# MG.net
KiCad netlist of a schematic drawn in EAGLE
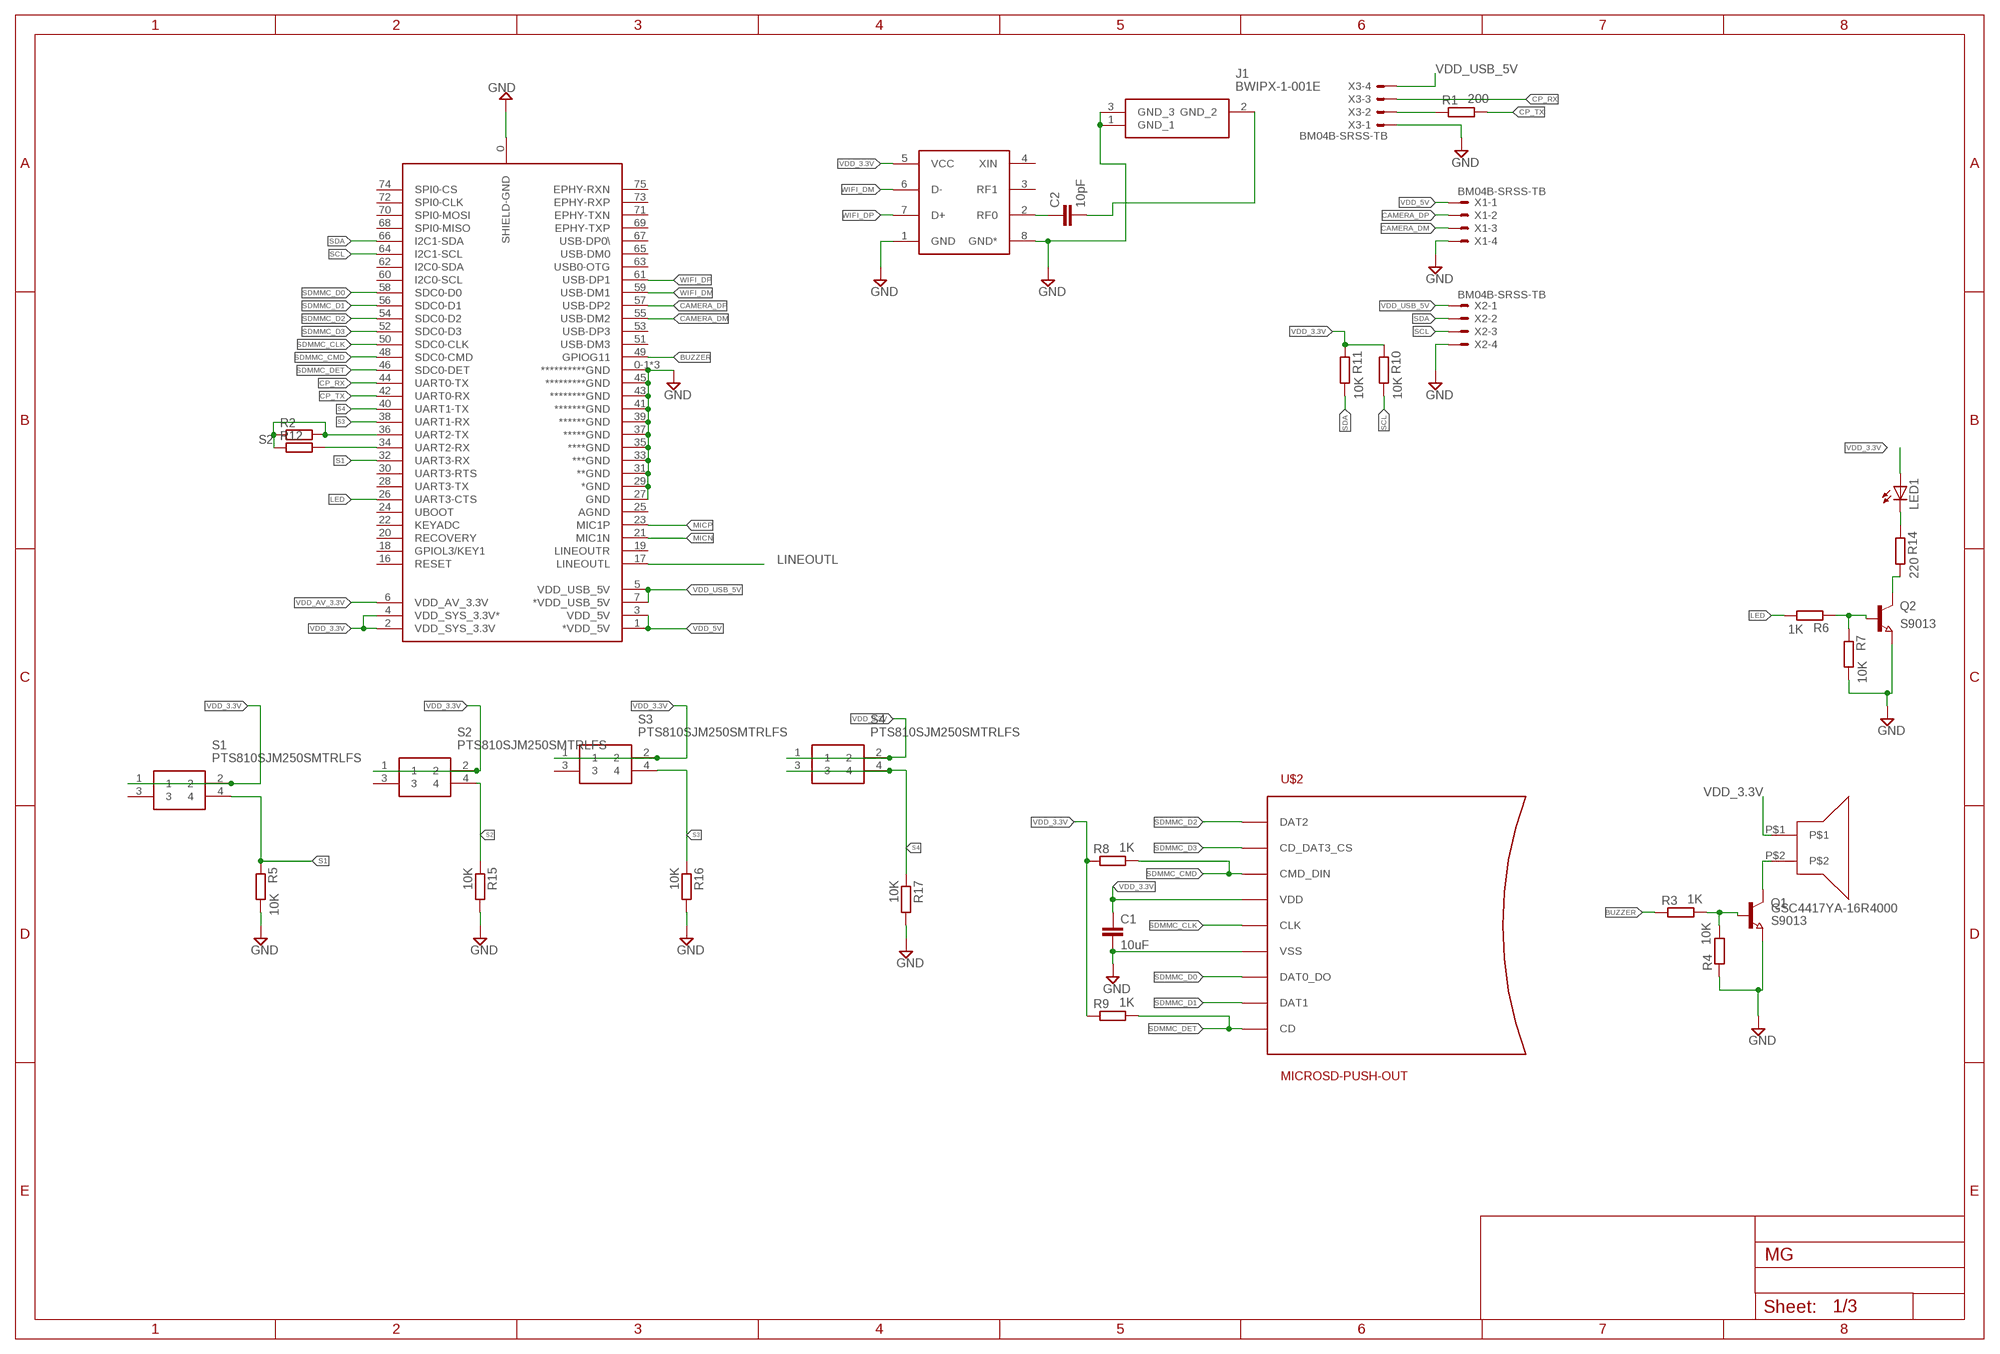
[diagram p0: schematic, sheet 1]
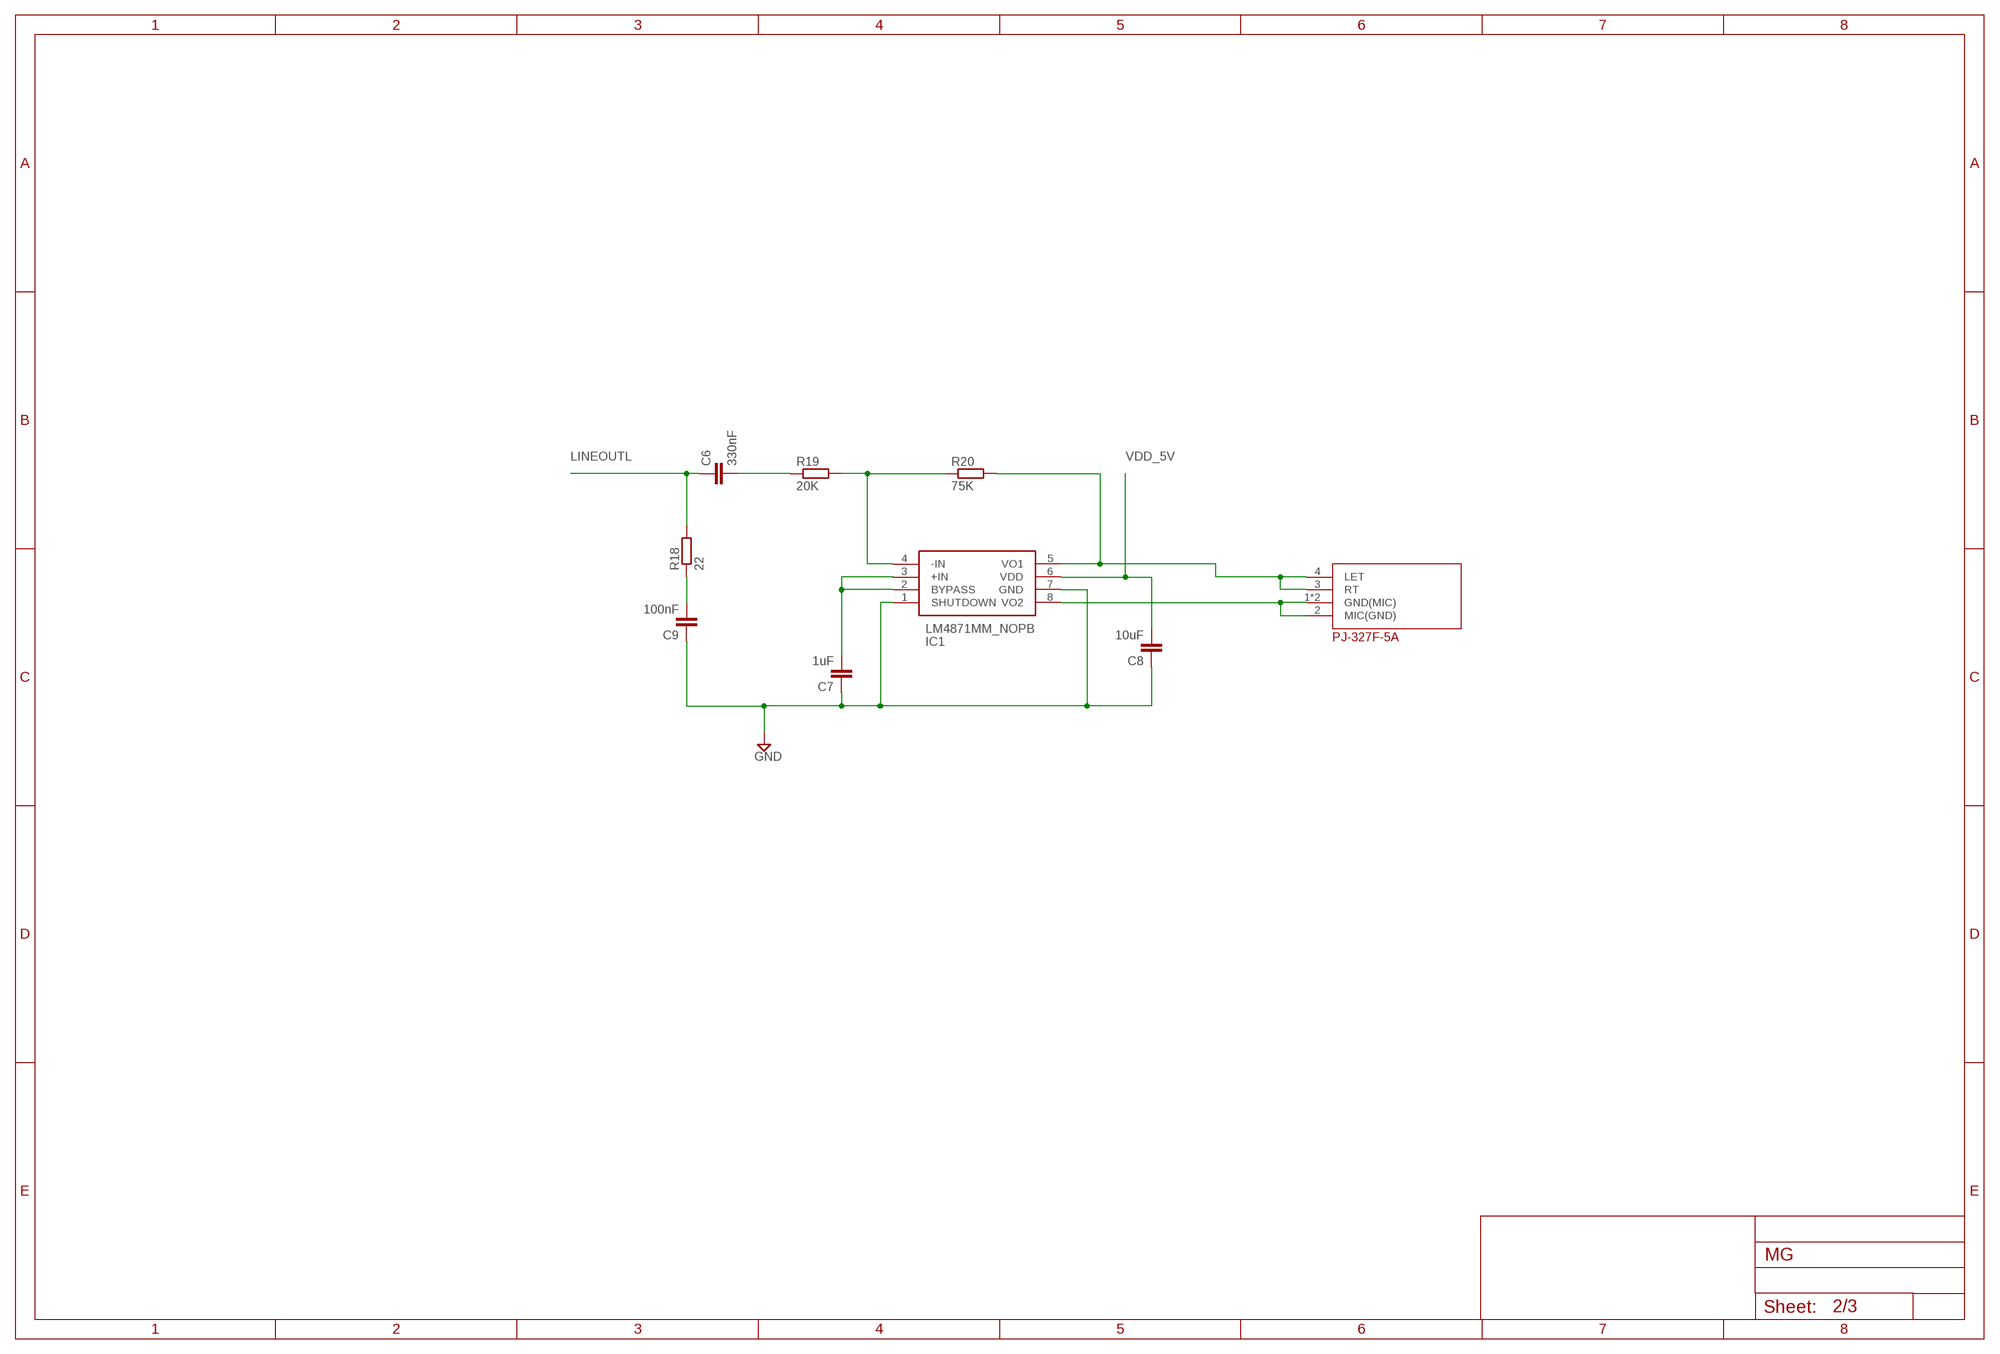
[diagram p1: schematic, sheet 2]
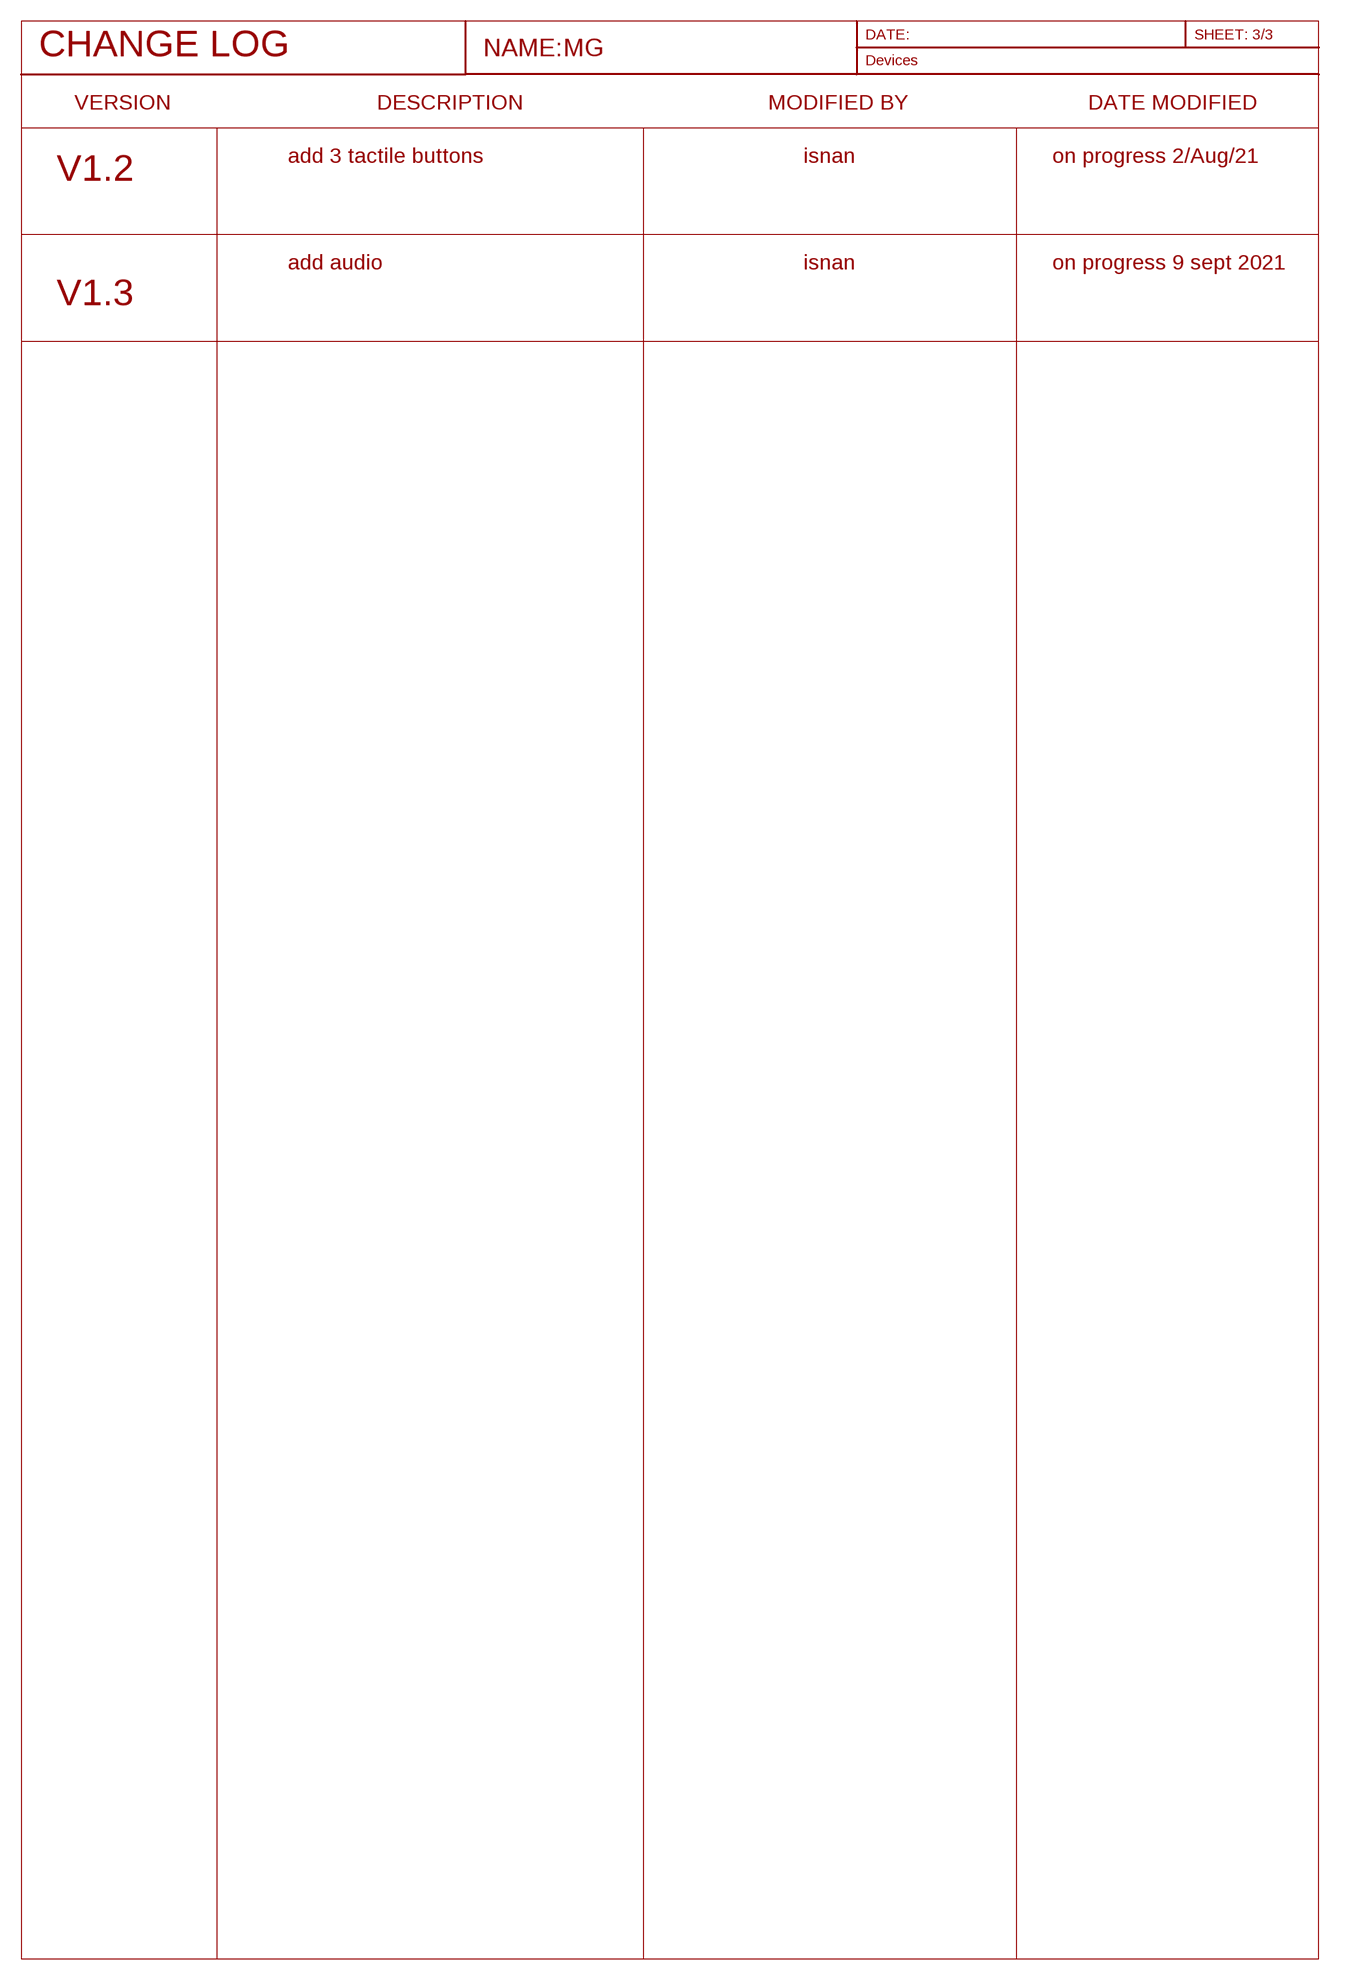
[diagram p2: schematic, sheet 3]

(export (version "E")
  (design (tool "Eeschema 10.0.6"))
  (components
    (comp (ref "C6")
      (value "330nF")
      (footprint "eagle-import:C0603")
      (libsource (lib "eagle-import") (part "C-EUC0603"))
    )
    (comp (ref "C7")
      (value "1uF")
      (footprint "eagle-import:C0603")
      (libsource (lib "eagle-import") (part "C-EUC0603"))
    )
    (comp (ref "C8")
      (value "10uF")
      (footprint "eagle-import:C0603")
      (libsource (lib "eagle-import") (part "C-EUC0603"))
    )
    (comp (ref "C9")
      (value "100nF")
      (footprint "eagle-import:C0603")
      (libsource (lib "eagle-import") (part "C-EUC0603"))
    )
    (comp (ref "IC1")
      (value "LM4871MM_NOPB")
      (footprint "eagle-import:SOP65P490X110-8N")
      (fields
        (field (name "MANUFACTURER_PART_NUMBER") "LM4871MM/NOPB")
        (field (name "MOUSER_PART_NUMBER") "926-LM4871MM/NOPB")
      )
      (libsource (lib "eagle-import") (part "LM4871MM_NOPB"))
    )
    (comp (ref "R18")
      (value "22")
      (footprint "eagle-import:R0603")
      (libsource (lib "eagle-import") (part "R-EU_R0603"))
    )
    (comp (ref "R19")
      (value "20K")
      (footprint "eagle-import:R0603")
      (libsource (lib "eagle-import") (part "R-EU_R0603"))
    )
    (comp (ref "R20")
      (value "75K")
      (footprint "eagle-import:R0603")
      (libsource (lib "eagle-import") (part "R-EU_R0603"))
    )
    (comp (ref "U$7")
      (value "PJ-327F-5A")
      (footprint "eagle-import:PJ-327F-5A")
      (libsource (lib "eagle-import") (part "PJ-327F-5A"))
    )
    (comp (ref "C1")
      (value "10uF")
      (footprint "eagle-import:C0603")
      (libsource (lib "eagle-import") (part "C-EUC0603"))
    )
    (comp (ref "C2")
      (value "10pF")
      (footprint "eagle-import:C0603")
      (libsource (lib "eagle-import") (part "C-EUC0603"))
    )
    (comp (ref "J1")
      (value "BWIPX-1-001E")
      (footprint "eagle-import:BWIPX1001E")
      (libsource (lib "eagle-import") (part "BWIPX-1-001E"))
    )
    (comp (ref "LED1")
      (value "LEDSML0603")
      (footprint "eagle-import:SML0603")
      (libsource (lib "eagle-import") (part "LEDSML0603"))
    )
    (comp (ref "Q1")
      (value "S9013")
      (footprint "eagle-import:SOT23")
      (libsource (lib "eagle-import") (part "NPN-TRANSISTOR_SOT23"))
    )
    (comp (ref "Q2")
      (value "S9013")
      (footprint "eagle-import:SOT23")
      (libsource (lib "eagle-import") (part "NPN-TRANSISTOR_SOT23"))
    )
    (comp (ref "R1")
      (value "200")
      (footprint "eagle-import:R0603")
      (libsource (lib "eagle-import") (part "R-EU_R0603"))
    )
    (comp (ref "R2")
      (value "R-EU_R0201")
      (footprint "eagle-import:R0201")
      (libsource (lib "eagle-import") (part "R-EU_R0201"))
    )
    (comp (ref "R3")
      (value "1K")
      (footprint "eagle-import:R0603")
      (libsource (lib "eagle-import") (part "R-EU_R0603"))
    )
    (comp (ref "R4")
      (value "10K")
      (footprint "eagle-import:R0603")
      (libsource (lib "eagle-import") (part "R-EU_R0603"))
    )
    (comp (ref "R5")
      (value "10K")
      (footprint "eagle-import:R0603")
      (libsource (lib "eagle-import") (part "R-EU_R0603"))
    )
    (comp (ref "R6")
      (value "1K")
      (footprint "eagle-import:R0603")
      (libsource (lib "eagle-import") (part "R-EU_R0603"))
    )
    (comp (ref "R7")
      (value "10K")
      (footprint "eagle-import:R0603")
      (libsource (lib "eagle-import") (part "R-EU_R0603"))
    )
    (comp (ref "R8")
      (value "1K")
      (footprint "eagle-import:R0603")
      (libsource (lib "eagle-import") (part "R-EU_R0603"))
    )
    (comp (ref "R9")
      (value "1K")
      (footprint "eagle-import:R0603")
      (libsource (lib "eagle-import") (part "R-EU_R0603"))
    )
    (comp (ref "R10")
      (value "10K")
      (footprint "eagle-import:R0603")
      (libsource (lib "eagle-import") (part "R-EU_R0603"))
    )
    (comp (ref "R11")
      (value "10K")
      (footprint "eagle-import:R0603")
      (libsource (lib "eagle-import") (part "R-EU_R0603"))
    )
    (comp (ref "R12")
      (value "R-EU_R0201")
      (footprint "eagle-import:R0201")
      (libsource (lib "eagle-import") (part "R-EU_R0201"))
    )
    (comp (ref "R14")
      (value "220")
      (footprint "eagle-import:R0603")
      (libsource (lib "eagle-import") (part "R-EU_R0603"))
    )
    (comp (ref "R15")
      (value "10K")
      (footprint "eagle-import:R0603")
      (libsource (lib "eagle-import") (part "R-EU_R0603"))
    )
    (comp (ref "R16")
      (value "10K")
      (footprint "eagle-import:R0603")
      (libsource (lib "eagle-import") (part "R-EU_R0603"))
    )
    (comp (ref "R17")
      (value "10K")
      (footprint "eagle-import:R0603")
      (libsource (lib "eagle-import") (part "R-EU_R0603"))
    )
    (comp (ref "S1")
      (value "PTS810SJM250SMTRLFS")
      (footprint "eagle-import:PTS810SJG250SMTRLFS")
      (fields (field (name "MOUSER_PART_NUMBER") "611-PTS810SJM250SMTR"))
      (libsource (lib "eagle-import") (part "PTS810SJM250SMTRLFS"))
    )
    (comp (ref "S2")
      (value "PTS810SJM250SMTRLFS")
      (footprint "eagle-import:PTS810SJG250SMTRLFS")
      (fields (field (name "MOUSER_PART_NUMBER") "611-PTS810SJM250SMTR"))
      (libsource (lib "eagle-import") (part "PTS810SJM250SMTRLFS"))
    )
    (comp (ref "S3")
      (value "PTS810SJM250SMTRLFS")
      (footprint "eagle-import:PTS810SJG250SMTRLFS")
      (fields (field (name "MOUSER_PART_NUMBER") "611-PTS810SJM250SMTR"))
      (libsource (lib "eagle-import") (part "PTS810SJM250SMTRLFS"))
    )
    (comp (ref "S4")
      (value "PTS810SJM250SMTRLFS")
      (footprint "eagle-import:PTS810SJG250SMTRLFS")
      (fields (field (name "MOUSER_PART_NUMBER") "611-PTS810SJM250SMTR"))
      (libsource (lib "eagle-import") (part "PTS810SJM250SMTRLFS"))
    )
    (comp (ref "U$1")
      (value "QUANTUM-CORE")
      (footprint "eagle-import:QUANTUM-QUARK-N")
      (libsource (lib "eagle-import") (part "QUANTUM-CORE"))
    )
    (comp (ref "U$2")
      (value "MICROSD-PUSH-OUT")
      (footprint "eagle-import:MICROSD-PUSH-OUT")
      (libsource (lib "eagle-import") (part "MICROSD-PUSH-OUT"))
    )
    (comp (ref "U$3")
      (value "WIFI-BT-RTL8723BU")
      (footprint "eagle-import:USB-WIFI-BT-RTL8723BU")
      (libsource (lib "eagle-import") (part "WIFI-BT-RTL8723BU"))
    )
    (comp (ref "U$4")
      (value "GSC4417YA-16R4000")
      (footprint "eagle-import:GSC4417YA-16R4000")
      (libsource (lib "eagle-import") (part "GSC4417YA-16R4000"))
    )
    (comp (ref "X1")
      (value "BM04B-SRSS-TB")
      (footprint "eagle-import:BM04B-SRSS-TB")
      (libsource (lib "eagle-import") (part "?M04B-SRSS-TBB"))
    )
    (comp (ref "X2")
      (value "BM04B-SRSS-TB")
      (footprint "eagle-import:BM04B-SRSS-TB")
      (libsource (lib "eagle-import") (part "?M04B-SRSS-TBB"))
    )
    (comp (ref "X3")
      (value "BM04B-SRSS-TB")
      (footprint "eagle-import:BM04B-SRSS-TB")
      (libsource (lib "eagle-import") (part "?M04B-SRSS-TBB"))
    )
  )
  (nets
    (net (code "1") (name "BUZZER") (class "Default")
      (node (ref "R3") (pin "1") (pinfunction "1_1") (pintype "passive"))
      (node (ref "U$1") (pin "49") (pinfunction "GPIOG11_49") (pintype "bidirectional"))
    )
    (net (code "2") (name "CAMERA_DM") (class "Default")
      (node (ref "U$1") (pin "55") (pinfunction "USB-DM2_55") (pintype "bidirectional"))
      (node (ref "X1") (pin "3") (pinfunction "S_3") (pintype "passive"))
    )
    (net (code "3") (name "CAMERA_DP") (class "Default")
      (node (ref "U$1") (pin "57") (pinfunction "USB-DP2_57") (pintype "bidirectional"))
      (node (ref "X1") (pin "2") (pinfunction "S_2") (pintype "passive"))
    )
    (net (code "4") (name "CP_RX") (class "Default")
      (node (ref "U$1") (pin "44") (pinfunction "UART0-TX_44") (pintype "bidirectional"))
      (node (ref "X3") (pin "3") (pinfunction "S_3") (pintype "passive"))
    )
    (net (code "5") (name "CP_TX") (class "Default")
      (node (ref "R1") (pin "2") (pinfunction "2_2") (pintype "passive"))
      (node (ref "U$1") (pin "42") (pinfunction "UART0-RX_42") (pintype "bidirectional"))
    )
    (net (code "6") (name "GND") (class "Default")
      (node (ref "C1") (pin "2") (pinfunction "2_2") (pintype "passive"))
      (node (ref "C7") (pin "1") (pinfunction "1_1") (pintype "passive"))
      (node (ref "C8") (pin "1") (pinfunction "1_1") (pintype "passive"))
      (node (ref "C9") (pin "1") (pinfunction "1_1") (pintype "passive"))
      (node (ref "IC1") (pin "1") (pinfunction "SHUTDOWN_1") (pintype "bidirectional"))
      (node (ref "IC1") (pin "7") (pinfunction "GND_7") (pintype "bidirectional"))
      (node (ref "J1") (pin "1") (pinfunction "GND_1_1") (pintype "bidirectional"))
      (node (ref "J1") (pin "3") (pinfunction "GND_3_3") (pintype "bidirectional"))
      (node (ref "Q1") (pin "2") (pinfunction "E_2") (pintype "passive"))
      (node (ref "Q2") (pin "2") (pinfunction "E_2") (pintype "passive"))
      (node (ref "R15") (pin "2") (pinfunction "2_2") (pintype "passive"))
      (node (ref "R16") (pin "2") (pinfunction "2_2") (pintype "passive"))
      (node (ref "R17") (pin "2") (pinfunction "2_2") (pintype "passive"))
      (node (ref "R4") (pin "1") (pinfunction "1_1") (pintype "passive"))
      (node (ref "R5") (pin "2") (pinfunction "2_2") (pintype "passive"))
      (node (ref "R7") (pin "2") (pinfunction "2_2") (pintype "passive"))
      (node (ref "U$1") (pin "0") (pinfunction "SHIELD-GND_0") (pintype "bidirectional"))
      (node (ref "U$1") (pin "0-1") (pinfunction "**********GND_0-1") (pintype "bidirectional"))
      (node (ref "U$1") (pin "0-2") (pinfunction "**********GND_0-2") (pintype "bidirectional"))
      (node (ref "U$1") (pin "27") (pinfunction "GND_27") (pintype "bidirectional"))
      (node (ref "U$1") (pin "29") (pinfunction "*GND_29") (pintype "bidirectional"))
      (node (ref "U$1") (pin "31") (pinfunction "**GND_31") (pintype "bidirectional"))
      (node (ref "U$1") (pin "33") (pinfunction "***GND_33") (pintype "bidirectional"))
      (node (ref "U$1") (pin "35") (pinfunction "****GND_35") (pintype "bidirectional"))
      (node (ref "U$1") (pin "37") (pinfunction "*****GND_37") (pintype "bidirectional"))
      (node (ref "U$1") (pin "39") (pinfunction "******GND_39") (pintype "bidirectional"))
      (node (ref "U$1") (pin "41") (pinfunction "*******GND_41") (pintype "bidirectional"))
      (node (ref "U$1") (pin "43") (pinfunction "********GND_43") (pintype "bidirectional"))
      (node (ref "U$1") (pin "45") (pinfunction "*********GND_45") (pintype "bidirectional"))
      (node (ref "U$1") (pin "47") (pinfunction "**********GND_47") (pintype "bidirectional"))
      (node (ref "U$2") (pin "6") (pinfunction "VSS_6") (pintype "bidirectional"))
      (node (ref "U$2") (pin "G1") (pinfunction "VSS_G1") (pintype "bidirectional"))
      (node (ref "U$2") (pin "G2") (pinfunction "VSS_G2") (pintype "bidirectional"))
      (node (ref "U$2") (pin "G3") (pinfunction "VSS_G3") (pintype "bidirectional"))
      (node (ref "U$2") (pin "G4") (pinfunction "VSS_G4") (pintype "bidirectional"))
      (node (ref "U$3") (pin "1") (pinfunction "GND_1") (pintype "bidirectional"))
      (node (ref "U$3") (pin "8") (pinfunction "GND*_8") (pintype "bidirectional"))
      (node (ref "X1") (pin "4") (pinfunction "S_4") (pintype "passive"))
      (node (ref "X2") (pin "4") (pinfunction "S_4") (pintype "passive"))
      (node (ref "X3") (pin "1") (pinfunction "S_1") (pintype "passive"))
    )
    (net (code "7") (name "LED") (class "Default")
      (node (ref "R6") (pin "2") (pinfunction "2_2") (pintype "passive"))
      (node (ref "U$1") (pin "26") (pinfunction "UART3-CTS_26") (pintype "bidirectional"))
    )
    (net (code "8") (name "LINEOUTL") (class "Default")
      (node (ref "C6") (pin "1") (pinfunction "1_1") (pintype "passive"))
      (node (ref "R18") (pin "2") (pinfunction "2_2") (pintype "passive"))
      (node (ref "U$1") (pin "17") (pinfunction "LINEOUTL_17") (pintype "bidirectional"))
    )
    (net (code "9") (name "MICN") (class "Default")
      (node (ref "U$1") (pin "21") (pinfunction "MIC1N_21") (pintype "bidirectional"))
    )
    (net (code "10") (name "MICP") (class "Default")
      (node (ref "U$1") (pin "23") (pinfunction "MIC1P_23") (pintype "bidirectional"))
    )
    (net (code "11") (name "Net-(C6-Pad2)") (class "Default")
      (node (ref "C6") (pin "2") (pinfunction "2_2") (pintype "passive"))
      (node (ref "R19") (pin "1") (pinfunction "1_1") (pintype "passive"))
    )
    (net (code "12") (name "Net-(C9-Pad2)") (class "Default")
      (node (ref "C9") (pin "2") (pinfunction "2_2") (pintype "passive"))
      (node (ref "R18") (pin "1") (pinfunction "1_1") (pintype "passive"))
    )
    (net (code "13") (name "Net-(IC1-+IN)") (class "Default")
      (node (ref "C7") (pin "2") (pinfunction "2_2") (pintype "passive"))
      (node (ref "IC1") (pin "2") (pinfunction "BYPASS_2") (pintype "bidirectional"))
      (node (ref "IC1") (pin "3") (pinfunction "+IN_3") (pintype "bidirectional"))
    )
    (net (code "14") (name "Net-(IC1--IN)") (class "Default")
      (node (ref "IC1") (pin "4") (pinfunction "-IN_4") (pintype "bidirectional"))
      (node (ref "R19") (pin "2") (pinfunction "2_2") (pintype "passive"))
      (node (ref "R20") (pin "1") (pinfunction "1_1") (pintype "passive"))
    )
    (net (code "15") (name "Net-(IC1-VO1)") (class "Default")
      (node (ref "IC1") (pin "5") (pinfunction "VO1_5") (pintype "bidirectional"))
      (node (ref "R20") (pin "2") (pinfunction "2_2") (pintype "passive"))
      (node (ref "U$7") (pin "3") (pinfunction "RT_3") (pintype "bidirectional"))
      (node (ref "U$7") (pin "4") (pinfunction "LET_4") (pintype "bidirectional"))
    )
    (net (code "16") (name "Net-(IC1-VO2)") (class "Default")
      (node (ref "IC1") (pin "8") (pinfunction "VO2_8") (pintype "bidirectional"))
      (node (ref "U$7") (pin "1") (pinfunction "GND(MIC)_1") (pintype "bidirectional"))
      (node (ref "U$7") (pin "2") (pinfunction "MIC(GND)_2") (pintype "bidirectional"))
      (node (ref "U$7") (pin "5") (pinfunction "GND(MIC)_5") (pintype "bidirectional"))
    )
    (net (code "17") (name "Net-(J1-GND_2)") (class "Default")
      (node (ref "C2") (pin "2") (pinfunction "2_2") (pintype "passive"))
      (node (ref "J1") (pin "2") (pinfunction "GND_2_2") (pintype "bidirectional"))
    )
    (net (code "18") (name "Net-(LED1-PadC)") (class "Default")
      (node (ref "LED1") (pin "C") (pinfunction "C_C") (pintype "passive"))
      (node (ref "R14") (pin "1") (pinfunction "1_1") (pintype "passive"))
    )
    (net (code "19") (name "Net-(Q1-B)") (class "Default")
      (node (ref "Q1") (pin "1") (pinfunction "B_1") (pintype "passive"))
      (node (ref "R3") (pin "2") (pinfunction "2_2") (pintype "passive"))
      (node (ref "R4") (pin "2") (pinfunction "2_2") (pintype "passive"))
    )
    (net (code "20") (name "Net-(Q1-C)") (class "Default")
      (node (ref "Q1") (pin "3") (pinfunction "C_3") (pintype "passive"))
      (node (ref "U$4") (pin "P$2") (pinfunction "P$2_P$2") (pintype "bidirectional"))
    )
    (net (code "21") (name "Net-(Q2-B)") (class "Default")
      (node (ref "Q2") (pin "1") (pinfunction "B_1") (pintype "passive"))
      (node (ref "R6") (pin "1") (pinfunction "1_1") (pintype "passive"))
      (node (ref "R7") (pin "1") (pinfunction "1_1") (pintype "passive"))
    )
    (net (code "22") (name "Net-(Q2-C)") (class "Default")
      (node (ref "Q2") (pin "3") (pinfunction "C_3") (pintype "passive"))
      (node (ref "R14") (pin "2") (pinfunction "2_2") (pintype "passive"))
    )
    (net (code "23") (name "Net-(U$1-UART2-RX)") (class "Default")
      (node (ref "R12") (pin "2") (pinfunction "2_2") (pintype "passive"))
      (node (ref "U$1") (pin "34") (pinfunction "UART2-RX_34") (pintype "bidirectional"))
    )
    (net (code "24") (name "Net-(U$3-RF0)") (class "Default")
      (node (ref "C2") (pin "1") (pinfunction "1_1") (pintype "passive"))
      (node (ref "U$3") (pin "2") (pinfunction "RF0_2") (pintype "bidirectional"))
    )
    (net (code "25") (name "Net-(X3B-S)") (class "Default")
      (node (ref "R1") (pin "1") (pinfunction "1_1") (pintype "passive"))
      (node (ref "X3") (pin "2") (pinfunction "S_2") (pintype "passive"))
    )
    (net (code "26") (name "S1") (class "Default")
      (node (ref "R5") (pin "1") (pinfunction "1_1") (pintype "passive"))
      (node (ref "S1") (pin "4") (pinfunction "4_4") (pintype "bidirectional"))
      (node (ref "U$1") (pin "32") (pinfunction "UART3-RX_32") (pintype "bidirectional"))
    )
    (net (code "27") (name "S2") (class "Default")
      (node (ref "R12") (pin "1") (pinfunction "1_1") (pintype "passive"))
      (node (ref "R15") (pin "1") (pinfunction "1_1") (pintype "passive"))
      (node (ref "R2") (pin "1") (pinfunction "1_1") (pintype "passive"))
      (node (ref "R2") (pin "2") (pinfunction "2_2") (pintype "passive"))
      (node (ref "S2") (pin "4") (pinfunction "4_4") (pintype "bidirectional"))
      (node (ref "U$1") (pin "36") (pinfunction "UART2-TX_36") (pintype "bidirectional"))
    )
    (net (code "28") (name "S3") (class "Default")
      (node (ref "R16") (pin "1") (pinfunction "1_1") (pintype "passive"))
      (node (ref "S3") (pin "4") (pinfunction "4_4") (pintype "bidirectional"))
      (node (ref "U$1") (pin "38") (pinfunction "UART1-RX_38") (pintype "bidirectional"))
    )
    (net (code "29") (name "S4") (class "Default")
      (node (ref "R17") (pin "1") (pinfunction "1_1") (pintype "passive"))
      (node (ref "S4") (pin "3") (pinfunction "3_3") (pintype "bidirectional"))
      (node (ref "S4") (pin "4") (pinfunction "4_4") (pintype "bidirectional"))
      (node (ref "U$1") (pin "40") (pinfunction "UART1-TX_40") (pintype "bidirectional"))
    )
    (net (code "30") (name "SCL") (class "Default")
      (node (ref "R10") (pin "2") (pinfunction "2_2") (pintype "passive"))
      (node (ref "U$1") (pin "64") (pinfunction "I2C1-SCL_64") (pintype "bidirectional"))
      (node (ref "X2") (pin "3") (pinfunction "S_3") (pintype "passive"))
    )
    (net (code "31") (name "SDA") (class "Default")
      (node (ref "R11") (pin "2") (pinfunction "2_2") (pintype "passive"))
      (node (ref "U$1") (pin "66") (pinfunction "I2C1-SDA_66") (pintype "bidirectional"))
      (node (ref "X2") (pin "2") (pinfunction "S_2") (pintype "passive"))
    )
    (net (code "32") (name "SDMMC_CLK") (class "Default")
      (node (ref "U$1") (pin "50") (pinfunction "SDC0-CLK_50") (pintype "bidirectional"))
      (node (ref "U$2") (pin "5") (pinfunction "CLK_5") (pintype "bidirectional"))
    )
    (net (code "33") (name "SDMMC_CMD") (class "Default")
      (node (ref "R8") (pin "2") (pinfunction "2_2") (pintype "passive"))
      (node (ref "U$1") (pin "48") (pinfunction "SDC0-CMD_48") (pintype "bidirectional"))
      (node (ref "U$2") (pin "3") (pinfunction "CMD_DIN_3") (pintype "bidirectional"))
    )
    (net (code "34") (name "SDMMC_D0") (class "Default")
      (node (ref "U$1") (pin "58") (pinfunction "SDC0-D0_58") (pintype "bidirectional"))
      (node (ref "U$2") (pin "7") (pinfunction "DAT0_DO_7") (pintype "bidirectional"))
    )
    (net (code "35") (name "SDMMC_D1") (class "Default")
      (node (ref "U$1") (pin "56") (pinfunction "SDC0-D1_56") (pintype "bidirectional"))
      (node (ref "U$2") (pin "8") (pinfunction "DAT1_8") (pintype "bidirectional"))
    )
    (net (code "36") (name "SDMMC_D2") (class "Default")
      (node (ref "U$1") (pin "54") (pinfunction "SDC0-D2_54") (pintype "bidirectional"))
      (node (ref "U$2") (pin "1") (pinfunction "DAT2_1") (pintype "bidirectional"))
    )
    (net (code "37") (name "SDMMC_D3") (class "Default")
      (node (ref "U$1") (pin "52") (pinfunction "SDC0-D3_52") (pintype "bidirectional"))
      (node (ref "U$2") (pin "2") (pinfunction "CD_DAT3_CS_2") (pintype "bidirectional"))
    )
    (net (code "38") (name "SDMMC_DET") (class "Default")
      (node (ref "R9") (pin "2") (pinfunction "2_2") (pintype "passive"))
      (node (ref "U$1") (pin "46") (pinfunction "SDC0-DET_46") (pintype "bidirectional"))
      (node (ref "U$2") (pin "CD") (pinfunction "CD_CD") (pintype "bidirectional"))
    )
    (net (code "39") (name "VDD_3.3V") (class "Default")
      (node (ref "C1") (pin "1") (pinfunction "1_1") (pintype "passive"))
      (node (ref "LED1") (pin "A") (pinfunction "A_A") (pintype "passive"))
      (node (ref "R10") (pin "1") (pinfunction "1_1") (pintype "passive"))
      (node (ref "R11") (pin "1") (pinfunction "1_1") (pintype "passive"))
      (node (ref "R8") (pin "1") (pinfunction "1_1") (pintype "passive"))
      (node (ref "R9") (pin "1") (pinfunction "1_1") (pintype "passive"))
      (node (ref "S1") (pin "1") (pinfunction "1_1") (pintype "bidirectional"))
      (node (ref "S1") (pin "2") (pinfunction "2_2") (pintype "bidirectional"))
      (node (ref "S2") (pin "1") (pinfunction "1_1") (pintype "bidirectional"))
      (node (ref "S2") (pin "2") (pinfunction "2_2") (pintype "bidirectional"))
      (node (ref "S3") (pin "1") (pinfunction "1_1") (pintype "bidirectional"))
      (node (ref "S3") (pin "2") (pinfunction "2_2") (pintype "bidirectional"))
      (node (ref "S4") (pin "1") (pinfunction "1_1") (pintype "bidirectional"))
      (node (ref "S4") (pin "2") (pinfunction "2_2") (pintype "bidirectional"))
      (node (ref "U$1") (pin "2") (pinfunction "VDD_SYS_3.3V_2") (pintype "bidirectional"))
      (node (ref "U$1") (pin "4") (pinfunction "VDD_SYS_3.3V*_4") (pintype "bidirectional"))
      (node (ref "U$2") (pin "4") (pinfunction "VDD_4") (pintype "bidirectional"))
      (node (ref "U$3") (pin "5") (pinfunction "VCC_5") (pintype "bidirectional"))
      (node (ref "U$4") (pin "P$1") (pinfunction "P$1_P$1") (pintype "bidirectional"))
    )
    (net (code "40") (name "VDD_5V") (class "Default")
      (node (ref "C8") (pin "2") (pinfunction "2_2") (pintype "passive"))
      (node (ref "IC1") (pin "6") (pinfunction "VDD_6") (pintype "bidirectional"))
      (node (ref "U$1") (pin "1") (pinfunction "*VDD_5V_1") (pintype "bidirectional"))
      (node (ref "U$1") (pin "3") (pinfunction "VDD_5V_3") (pintype "bidirectional"))
      (node (ref "X1") (pin "1") (pinfunction "S_1") (pintype "passive"))
    )
    (net (code "41") (name "VDD_AV_3.3V") (class "Default")
      (node (ref "U$1") (pin "6") (pinfunction "VDD_AV_3.3V_6") (pintype "bidirectional"))
    )
    (net (code "42") (name "VDD_USB_5V") (class "Default")
      (node (ref "U$1") (pin "5") (pinfunction "VDD_USB_5V_5") (pintype "bidirectional"))
      (node (ref "U$1") (pin "7") (pinfunction "*VDD_USB_5V_7") (pintype "bidirectional"))
      (node (ref "X2") (pin "1") (pinfunction "S_1") (pintype "passive"))
      (node (ref "X3") (pin "4") (pinfunction "S_4") (pintype "passive"))
    )
    (net (code "43") (name "WIFI_DM") (class "Default")
      (node (ref "U$1") (pin "59") (pinfunction "USB-DM1_59") (pintype "bidirectional"))
      (node (ref "U$3") (pin "6") (pinfunction "D-_6") (pintype "bidirectional"))
    )
    (net (code "44") (name "WIFI_DP") (class "Default")
      (node (ref "U$1") (pin "61") (pinfunction "USB-DP1_61") (pintype "bidirectional"))
      (node (ref "U$3") (pin "7") (pinfunction "D+_7") (pintype "bidirectional"))
    )
    (net (code "45") (name "unconnected-(S1-Pad3)") (class "Default")
      (node (ref "S1") (pin "3") (pinfunction "3_3") (pintype "bidirectional"))
    )
    (net (code "46") (name "unconnected-(S2-Pad3)") (class "Default")
      (node (ref "S2") (pin "3") (pinfunction "3_3") (pintype "bidirectional"))
    )
    (net (code "47") (name "unconnected-(S3-Pad3)") (class "Default")
      (node (ref "S3") (pin "3") (pinfunction "3_3") (pintype "bidirectional"))
    )
    (net (code "48") (name "unconnected-(U$1-AGND-Pad25)") (class "Default")
      (node (ref "U$1") (pin "25") (pinfunction "AGND_25") (pintype "bidirectional"))
    )
    (net (code "49") (name "unconnected-(U$1-EPHY-RXN-Pad75)") (class "Default")
      (node (ref "U$1") (pin "75") (pinfunction "EPHY-RXN_75") (pintype "bidirectional"))
    )
    (net (code "50") (name "unconnected-(U$1-EPHY-RXP-Pad73)") (class "Default")
      (node (ref "U$1") (pin "73") (pinfunction "EPHY-RXP_73") (pintype "bidirectional"))
    )
    (net (code "51") (name "unconnected-(U$1-EPHY-TXN-Pad71)") (class "Default")
      (node (ref "U$1") (pin "71") (pinfunction "EPHY-TXN_71") (pintype "bidirectional"))
    )
    (net (code "52") (name "unconnected-(U$1-EPHY-TXP-Pad69)") (class "Default")
      (node (ref "U$1") (pin "69") (pinfunction "EPHY-TXP_69") (pintype "bidirectional"))
    )
    (net (code "53") (name "unconnected-(U$1-GPIOL3{slash}KEY1-Pad18)") (class "Default")
      (node (ref "U$1") (pin "18") (pinfunction "GPIOL3/KEY1_18") (pintype "bidirectional"))
    )
    (net (code "54") (name "unconnected-(U$1-I2C0-SCL-Pad60)") (class "Default")
      (node (ref "U$1") (pin "60") (pinfunction "I2C0-SCL_60") (pintype "bidirectional"))
    )
    (net (code "55") (name "unconnected-(U$1-I2C0-SDA-Pad62)") (class "Default")
      (node (ref "U$1") (pin "62") (pinfunction "I2C0-SDA_62") (pintype "bidirectional"))
    )
    (net (code "56") (name "unconnected-(U$1-KEYADC-Pad22)") (class "Default")
      (node (ref "U$1") (pin "22") (pinfunction "KEYADC_22") (pintype "bidirectional"))
    )
    (net (code "57") (name "unconnected-(U$1-LINEOUTR-Pad19)") (class "Default")
      (node (ref "U$1") (pin "19") (pinfunction "LINEOUTR_19") (pintype "bidirectional"))
    )
    (net (code "58") (name "unconnected-(U$1-RECOVERY-Pad20)") (class "Default")
      (node (ref "U$1") (pin "20") (pinfunction "RECOVERY_20") (pintype "bidirectional"))
    )
    (net (code "59") (name "unconnected-(U$1-RESET-Pad16)") (class "Default")
      (node (ref "U$1") (pin "16") (pinfunction "RESET_16") (pintype "bidirectional"))
    )
    (net (code "60") (name "unconnected-(U$1-SPI0-CLK-Pad72)") (class "Default")
      (node (ref "U$1") (pin "72") (pinfunction "SPI0-CLK_72") (pintype "bidirectional"))
    )
    (net (code "61") (name "unconnected-(U$1-SPI0-CS-Pad74)") (class "Default")
      (node (ref "U$1") (pin "74") (pinfunction "SPI0-CS_74") (pintype "bidirectional"))
    )
    (net (code "62") (name "unconnected-(U$1-SPI0-MISO-Pad68)") (class "Default")
      (node (ref "U$1") (pin "68") (pinfunction "SPI0-MISO_68") (pintype "bidirectional"))
    )
    (net (code "63") (name "unconnected-(U$1-SPI0-MOSI-Pad70)") (class "Default")
      (node (ref "U$1") (pin "70") (pinfunction "SPI0-MOSI_70") (pintype "bidirectional"))
    )
    (net (code "64") (name "unconnected-(U$1-UART3-RTS-Pad30)") (class "Default")
      (node (ref "U$1") (pin "30") (pinfunction "UART3-RTS_30") (pintype "bidirectional"))
    )
    (net (code "65") (name "unconnected-(U$1-UART3-TX-Pad28)") (class "Default")
      (node (ref "U$1") (pin "28") (pinfunction "UART3-TX_28") (pintype "bidirectional"))
    )
    (net (code "66") (name "unconnected-(U$1-UBOOT-Pad24)") (class "Default")
      (node (ref "U$1") (pin "24") (pinfunction "UBOOT_24") (pintype "bidirectional"))
    )
    (net (code "67") (name "unconnected-(U$1-USB-DM0-Pad65)") (class "Default")
      (node (ref "U$1") (pin "65") (pinfunction "USB-DM0_65") (pintype "bidirectional"))
    )
    (net (code "68") (name "unconnected-(U$1-USB-DM3-Pad51)") (class "Default")
      (node (ref "U$1") (pin "51") (pinfunction "USB-DM3_51") (pintype "bidirectional"))
    )
    (net (code "69") (name "unconnected-(U$1-USB-DP0\\-Pad67)") (class "Default")
      (node (ref "U$1") (pin "67") (pinfunction "USB-DP0\\_67") (pintype "bidirectional"))
    )
    (net (code "70") (name "unconnected-(U$1-USB-DP3-Pad53)") (class "Default")
      (node (ref "U$1") (pin "53") (pinfunction "USB-DP3_53") (pintype "bidirectional"))
    )
    (net (code "71") (name "unconnected-(U$1-USB0-OTG-Pad63)") (class "Default")
      (node (ref "U$1") (pin "63") (pinfunction "USB0-OTG_63") (pintype "bidirectional"))
    )
    (net (code "72") (name "unconnected-(U$3-RF1-Pad3)") (class "Default")
      (node (ref "U$3") (pin "3") (pinfunction "RF1_3") (pintype "bidirectional"))
    )
    (net (code "73") (name "unconnected-(U$3-XIN-Pad4)") (class "Default")
      (node (ref "U$3") (pin "4") (pinfunction "XIN_4") (pintype "bidirectional"))
    )
  )
)
